# pidplate-mk-2_1.net
KiCad netlist of a schematic drawn in EAGLE
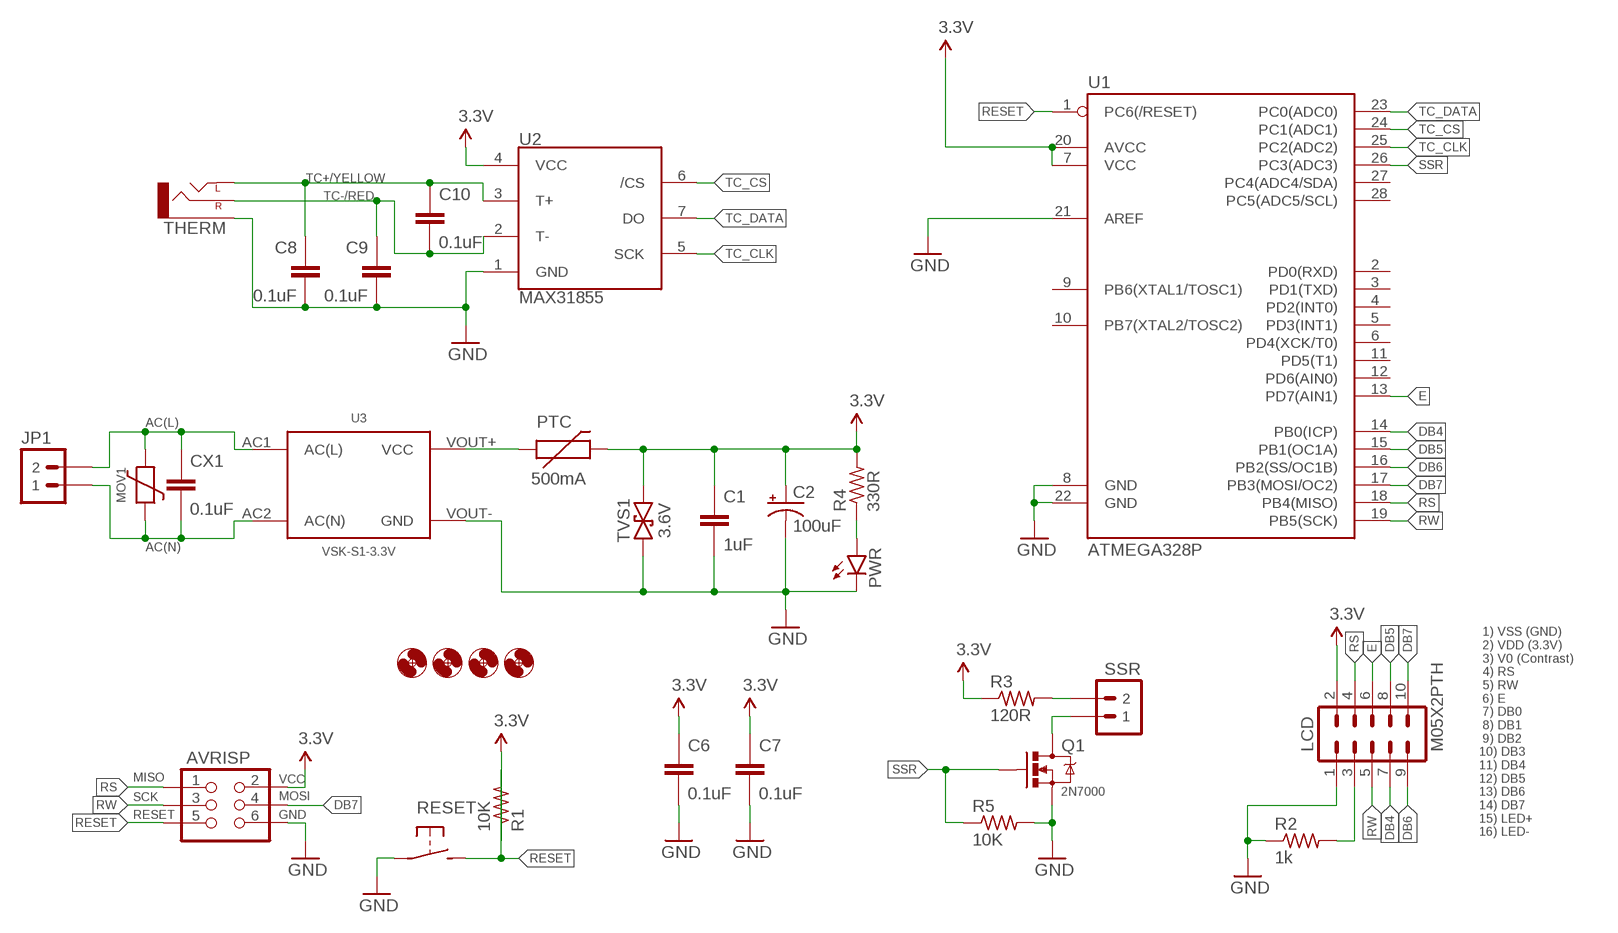
[diagram p0: schematic, sheet 1]

(export (version "E")
  (design (tool "Eeschema 10.0.6"))
  (components
    (comp (ref "AVRISP")
      (value "AVR_SPI_PRG_6PTH")
      (footprint "eagle-import:2X3")
      (libsource (lib "eagle-import") (part "AVR_SPI_PRG_6PTH"))
    )
    (comp (ref "C1")
      (value "1uF")
      (footprint "eagle-import:C025-024X044")
      (libsource (lib "eagle-import") (part "CAPACITOR-CERAMIC025-024X044"))
    )
    (comp (ref "C2")
      (value "100uF")
      (footprint "eagle-import:E2,5-7")
      (libsource (lib "eagle-import") (part "CAPACITOR-POLARIZEDE2.5-7"))
    )
    (comp (ref "C6")
      (value "0.1uF")
      (footprint "eagle-import:C025-024X044")
      (libsource (lib "eagle-import") (part "CAPACITOR-CERAMIC025-024X044"))
    )
    (comp (ref "C7")
      (value "0.1uF")
      (footprint "eagle-import:C025-024X044")
      (libsource (lib "eagle-import") (part "CAPACITOR-CERAMIC025-024X044"))
    )
    (comp (ref "C8")
      (value "0.1uF")
      (footprint "eagle-import:C025-024X044")
      (libsource (lib "eagle-import") (part "CAPACITOR-CERAMIC025-024X044"))
    )
    (comp (ref "C9")
      (value "0.1uF")
      (footprint "eagle-import:C025-024X044")
      (libsource (lib "eagle-import") (part "CAPACITOR-CERAMIC025-024X044"))
    )
    (comp (ref "C10")
      (value "0.1uF")
      (footprint "eagle-import:C025-024X044")
      (libsource (lib "eagle-import") (part "CAPACITOR-CERAMIC025-024X044"))
    )
    (comp (ref "CX1")
      (value "0.1uF")
      (footprint "eagle-import:XC10B5")
      (libsource (lib "eagle-import") (part "CXXC10B5"))
    )
    (comp (ref "H1")
      (value "HOLE#2")
      (footprint "eagle-import:HOLE-#2")
      (libsource (lib "eagle-import") (part "HOLE#2"))
    )
    (comp (ref "H2")
      (value "HOLE#2")
      (footprint "eagle-import:HOLE-#2")
      (libsource (lib "eagle-import") (part "HOLE#2"))
    )
    (comp (ref "H3")
      (value "HOLE#2")
      (footprint "eagle-import:HOLE-#2")
      (libsource (lib "eagle-import") (part "HOLE#2"))
    )
    (comp (ref "H4")
      (value "HOLE#2")
      (footprint "eagle-import:HOLE-#2")
      (libsource (lib "eagle-import") (part "HOLE#2"))
    )
    (comp (ref "JP1")
      (value "M023.5MM")
      (footprint "eagle-import:SCREWTERMINAL-3.5MM-2")
      (libsource (lib "eagle-import") (part "M023.5MM"))
    )
    (comp (ref "LCD")
      (value "M05X2PTH")
      (footprint "eagle-import:AVR_ICSP")
      (libsource (lib "eagle-import") (part "M05X2PTH"))
    )
    (comp (ref "MOV1")
      (value "VARISITORVAR-5.08MM-PTH")
      (footprint "eagle-import:VAR-5.08MM-PTH")
      (libsource (lib "eagle-import") (part "VARISITORVAR-5.08MM-PTH"))
    )
    (comp (ref "PTC")
      (value "500mA")
      (footprint "eagle-import:PTC")
      (libsource (lib "eagle-import") (part "PTCPTH"))
    )
    (comp (ref "PWR")
      (value "LED3MM")
      (footprint "eagle-import:LED3MM")
      (libsource (lib "eagle-import") (part "LED3MM"))
    )
    (comp (ref "Q1")
      (value "2N7000")
      (footprint "eagle-import:TO-92-AMMO")
      (libsource (lib "eagle-import") (part "MOSFET-NCHANNEL2N7000-AMMO"))
    )
    (comp (ref "R1")
      (value "10K")
      (footprint "eagle-import:RESISTOR-AXIAL-PTH-6.35MM")
      (libsource (lib "eagle-import") (part "RESISTORPTH-AXIAL-6.35MM"))
    )
    (comp (ref "R2")
      (value "1k")
      (footprint "eagle-import:RESISTOR-AXIAL-PTH-6.35MM")
      (libsource (lib "eagle-import") (part "RESISTORPTH-AXIAL-6.35MM"))
    )
    (comp (ref "R3")
      (value "120R")
      (footprint "eagle-import:RESISTOR-AXIAL-PTH-6.35MM")
      (libsource (lib "eagle-import") (part "RESISTORPTH-AXIAL-6.35MM"))
    )
    (comp (ref "R4")
      (value "330R")
      (footprint "eagle-import:RESISTOR-AXIAL-PTH-6.35MM")
      (libsource (lib "eagle-import") (part "RESISTORPTH-AXIAL-6.35MM"))
    )
    (comp (ref "R5")
      (value "10K")
      (footprint "eagle-import:RESISTOR-AXIAL-PTH-6.35MM")
      (libsource (lib "eagle-import") (part "RESISTORPTH-AXIAL-6.35MM"))
    )
    (comp (ref "RESET")
      (value "SPST-NO-TACT3MM-PTH-SMALL-PADS")
      (footprint "eagle-import:DTS-3-SMALL-PADS")
      (libsource (lib "eagle-import") (part "SPST-NO-TACT3MM-PTH-SMALL-PADS"))
    )
    (comp (ref "SSR")
      (value "M02JST-PTH-VERT")
      (footprint "eagle-import:JST-2-PH-VERT-PTH")
      (libsource (lib "eagle-import") (part "M02JST-PTH-VERT"))
    )
    (comp (ref "THERM")
      (value "AUDIO-JACK2.5MM")
      (footprint "eagle-import:STEREOJACK2.5MM_STEREOJACK2.5MM")
      (libsource (lib "eagle-import") (part "AUDIO-JACK2.5MM"))
    )
    (comp (ref "TVS1")
      (value "3.6V")
      (footprint "eagle-import:DO-41-TVS")
      (libsource (lib "eagle-import") (part "TVSDO-41-TVS-BIDIRECTIONAL"))
    )
    (comp (ref "U1")
      (value "ATMEGA328P")
      (footprint "eagle-import:DIL28-3")
      (libsource (lib "eagle-import") (part "ATMEGA328P_PDIP"))
    )
    (comp (ref "U2")
      (value "MAX31855")
      (footprint "eagle-import:SOIC127P600X175-8N")
      (libsource (lib "eagle-import") (part "MAX31855SOIC"))
    )
    (comp (ref "U3")
      (value "VSK-S1-3.3V")
      (footprint "eagle-import:VSK-S1")
      (libsource (lib "eagle-import") (part "VSK-S1"))
    )
  )
  (nets
    (net (code "1") (name "/AC(L)") (class "Default")
      (node (ref "CX1") (pin "1") (pinfunction "1_1") (pintype "passive"))
      (node (ref "JP1") (pin "2") (pinfunction "2_2") (pintype "passive"))
      (node (ref "MOV1") (pin "2") (pinfunction "P$2_2") (pintype "bidirectional"))
      (node (ref "U3") (pin "AC1") (pinfunction "AC(L)_AC1") (pintype "bidirectional"))
    )
    (net (code "2") (name "/AC(N)") (class "Default")
      (node (ref "CX1") (pin "2") (pinfunction "2_2") (pintype "passive"))
      (node (ref "JP1") (pin "1") (pinfunction "1_1") (pintype "passive"))
      (node (ref "MOV1") (pin "1") (pinfunction "P$1_1") (pintype "bidirectional"))
      (node (ref "U3") (pin "AC2") (pinfunction "AC(N)_AC2") (pintype "bidirectional"))
    )
    (net (code "3") (name "/TC+{slash}YELLOW") (class "Default")
      (node (ref "C10") (pin "1") (pinfunction "1_1") (pintype "passive"))
      (node (ref "C8") (pin "1") (pinfunction "1_1") (pintype "passive"))
      (node (ref "THERM") (pin "RING1") (pinfunction "LEFT_RING1") (pintype "bidirectional"))
      (node (ref "THERM") (pin "RING2") (pinfunction "LEFT_RING2") (pintype "bidirectional"))
      (node (ref "U2") (pin "3") (pinfunction "T+_3") (pintype "input"))
    )
    (net (code "4") (name "/TC-{slash}RED") (class "Default")
      (node (ref "C10") (pin "2") (pinfunction "2_2") (pintype "passive"))
      (node (ref "C9") (pin "1") (pinfunction "1_1") (pintype "passive"))
      (node (ref "THERM") (pin "TIP") (pinfunction "RIGHT_TIP") (pintype "bidirectional"))
      (node (ref "U2") (pin "2") (pinfunction "T-_2") (pintype "input"))
    )
    (net (code "5") (name "3.3V") (class "Default")
      (node (ref "AVRISP") (pin "2") (pinfunction "VCC_2") (pintype "passive"))
      (node (ref "C1") (pin "1") (pinfunction "1_1") (pintype "passive"))
      (node (ref "C2") (pin "+") (pinfunction "+_+") (pintype "passive"))
      (node (ref "C6") (pin "1") (pinfunction "1_1") (pintype "passive"))
      (node (ref "C7") (pin "1") (pinfunction "1_1") (pintype "passive"))
      (node (ref "LCD") (pin "2") (pinfunction "2_2") (pintype "passive"))
      (node (ref "PTC") (pin "P$2") (pinfunction "2_P$2") (pintype "bidirectional"))
      (node (ref "R1") (pin "P$1") (pinfunction "1_P$1") (pintype "passive"))
      (node (ref "R3") (pin "P$1") (pinfunction "1_P$1") (pintype "passive"))
      (node (ref "R4") (pin "P$2") (pinfunction "2_P$2") (pintype "passive"))
      (node (ref "TVS1") (pin "P$2") (pinfunction "2_P$2") (pintype "passive"))
      (node (ref "U1") (pin "20") (pinfunction "AVCC_20") (pintype "bidirectional"))
      (node (ref "U1") (pin "7") (pinfunction "VCC_7") (pintype "bidirectional"))
      (node (ref "U2") (pin "4") (pinfunction "VCC_4") (pintype "power_in"))
    )
    (net (code "6") (name "DB4") (class "Default")
      (node (ref "LCD") (pin "7") (pinfunction "7_7") (pintype "passive"))
      (node (ref "U1") (pin "14") (pinfunction "PB0(ICP)_14") (pintype "bidirectional"))
    )
    (net (code "7") (name "DB5") (class "Default")
      (node (ref "LCD") (pin "8") (pinfunction "8_8") (pintype "passive"))
      (node (ref "U1") (pin "15") (pinfunction "PB1(OC1A)_15") (pintype "bidirectional"))
    )
    (net (code "8") (name "DB6") (class "Default")
      (node (ref "LCD") (pin "9") (pinfunction "9_9") (pintype "passive"))
      (node (ref "U1") (pin "16") (pinfunction "PB2(SS/OC1B)_16") (pintype "bidirectional"))
    )
    (net (code "9") (name "DB7") (class "Default")
      (node (ref "AVRISP") (pin "4") (pinfunction "MOSI_4") (pintype "passive"))
      (node (ref "LCD") (pin "10") (pinfunction "10_10") (pintype "passive"))
      (node (ref "U1") (pin "17") (pinfunction "PB3(MOSI/OC2)_17") (pintype "bidirectional"))
    )
    (net (code "10") (name "E") (class "Default")
      (node (ref "LCD") (pin "6") (pinfunction "6_6") (pintype "passive"))
      (node (ref "U1") (pin "13") (pinfunction "PD7(AIN1)_13") (pintype "bidirectional"))
    )
    (net (code "11") (name "GND") (class "Default")
      (node (ref "AVRISP") (pin "6") (pinfunction "GND_6") (pintype "passive"))
      (node (ref "C1") (pin "2") (pinfunction "2_2") (pintype "passive"))
      (node (ref "C2") (pin "-") (pinfunction "-_-") (pintype "passive"))
      (node (ref "C6") (pin "2") (pinfunction "2_2") (pintype "passive"))
      (node (ref "C7") (pin "2") (pinfunction "2_2") (pintype "passive"))
      (node (ref "C8") (pin "2") (pinfunction "2_2") (pintype "passive"))
      (node (ref "C9") (pin "2") (pinfunction "2_2") (pintype "passive"))
      (node (ref "LCD") (pin "1") (pinfunction "1_1") (pintype "passive"))
      (node (ref "PWR") (pin "K") (pinfunction "C_K") (pintype "passive"))
      (node (ref "Q1") (pin "1") (pinfunction "S_1") (pintype "passive"))
      (node (ref "R2") (pin "P$1") (pinfunction "1_P$1") (pintype "passive"))
      (node (ref "R5") (pin "P$2") (pinfunction "2_P$2") (pintype "passive"))
      (node (ref "RESET") (pin "1") (pinfunction "1_1") (pintype "passive"))
      (node (ref "THERM") (pin "SHIELD") (pinfunction "SLEEVE_SHIELD") (pintype "bidirectional"))
      (node (ref "TVS1") (pin "P$1") (pinfunction "1_P$1") (pintype "passive"))
      (node (ref "U1") (pin "21") (pinfunction "AREF_21") (pintype "bidirectional"))
      (node (ref "U1") (pin "22") (pinfunction "GND_22") (pintype "bidirectional"))
      (node (ref "U1") (pin "8") (pinfunction "GND_8") (pintype "bidirectional"))
      (node (ref "U2") (pin "1") (pinfunction "GND_1") (pintype "power_in"))
      (node (ref "U3") (pin "VOUT-") (pinfunction "GND_VOUT-") (pintype "bidirectional"))
    )
    (net (code "12") (name "Net-(PTC-1)") (class "Default")
      (node (ref "PTC") (pin "P$1") (pinfunction "1_P$1") (pintype "bidirectional"))
      (node (ref "U3") (pin "VOUT+") (pinfunction "VCC_VOUT+") (pintype "bidirectional"))
    )
    (net (code "13") (name "Net-(Q1-D)") (class "Default")
      (node (ref "Q1") (pin "3") (pinfunction "D_3") (pintype "passive"))
      (node (ref "SSR") (pin "1") (pinfunction "1_1") (pintype "passive"))
    )
    (net (code "14") (name "Net-(R2-2)") (class "Default")
      (node (ref "LCD") (pin "3") (pinfunction "3_3") (pintype "passive"))
      (node (ref "R2") (pin "P$2") (pinfunction "2_P$2") (pintype "passive"))
    )
    (net (code "15") (name "Net-(R3-2)") (class "Default")
      (node (ref "R3") (pin "P$2") (pinfunction "2_P$2") (pintype "passive"))
      (node (ref "SSR") (pin "2") (pinfunction "2_2") (pintype "passive"))
    )
    (net (code "16") (name "Net-(R4-1)") (class "Default")
      (node (ref "PWR") (pin "A") (pinfunction "A_A") (pintype "passive"))
      (node (ref "R4") (pin "P$1") (pinfunction "1_P$1") (pintype "passive"))
    )
    (net (code "17") (name "RESET") (class "Default")
      (node (ref "AVRISP") (pin "5") (pinfunction "RESET_5") (pintype "passive"))
      (node (ref "R1") (pin "P$2") (pinfunction "2_P$2") (pintype "passive"))
      (node (ref "RESET") (pin "2") (pinfunction "2_2") (pintype "passive"))
      (node (ref "U1") (pin "1") (pinfunction "PC6(/RESET)_1") (pintype "bidirectional"))
    )
    (net (code "18") (name "RS") (class "Default")
      (node (ref "AVRISP") (pin "1") (pinfunction "MISO_1") (pintype "passive"))
      (node (ref "LCD") (pin "4") (pinfunction "4_4") (pintype "passive"))
      (node (ref "U1") (pin "18") (pinfunction "PB4(MISO)_18") (pintype "bidirectional"))
    )
    (net (code "19") (name "RW") (class "Default")
      (node (ref "AVRISP") (pin "3") (pinfunction "SCK_3") (pintype "passive"))
      (node (ref "LCD") (pin "5") (pinfunction "5_5") (pintype "passive"))
      (node (ref "U1") (pin "19") (pinfunction "PB5(SCK)_19") (pintype "bidirectional"))
    )
    (net (code "20") (name "SSR") (class "Default")
      (node (ref "Q1") (pin "2") (pinfunction "G_2") (pintype "passive"))
      (node (ref "R5") (pin "P$1") (pinfunction "1_P$1") (pintype "passive"))
      (node (ref "U1") (pin "26") (pinfunction "PC3(ADC3)_26") (pintype "bidirectional"))
    )
    (net (code "21") (name "TC_CLK") (class "Default")
      (node (ref "U1") (pin "25") (pinfunction "PC2(ADC2)_25") (pintype "bidirectional"))
      (node (ref "U2") (pin "5") (pinfunction "SCK_5") (pintype "input"))
    )
    (net (code "22") (name "TC_CS") (class "Default")
      (node (ref "U1") (pin "24") (pinfunction "PC1(ADC1)_24") (pintype "bidirectional"))
      (node (ref "U2") (pin "6") (pinfunction "/CS_6") (pintype "input"))
    )
    (net (code "23") (name "TC_DATA") (class "Default")
      (node (ref "U1") (pin "23") (pinfunction "PC0(ADC0)_23") (pintype "bidirectional"))
      (node (ref "U2") (pin "7") (pinfunction "DO_7") (pintype "output"))
    )
    (net (code "24") (name "unconnected-(U1-PB6(XTAL1{slash}TOSC1)-Pad9)") (class "Default")
      (node (ref "U1") (pin "9") (pinfunction "PB6(XTAL1/TOSC1)_9") (pintype "bidirectional"))
    )
    (net (code "25") (name "unconnected-(U1-PB7(XTAL2{slash}TOSC2)-Pad10)") (class "Default")
      (node (ref "U1") (pin "10") (pinfunction "PB7(XTAL2/TOSC2)_10") (pintype "bidirectional"))
    )
    (net (code "26") (name "unconnected-(U1-PC4(ADC4{slash}SDA)-Pad27)") (class "Default")
      (node (ref "U1") (pin "27") (pinfunction "PC4(ADC4/SDA)_27") (pintype "bidirectional"))
    )
    (net (code "27") (name "unconnected-(U1-PC5(ADC5{slash}SCL)-Pad28)") (class "Default")
      (node (ref "U1") (pin "28") (pinfunction "PC5(ADC5/SCL)_28") (pintype "bidirectional"))
    )
    (net (code "28") (name "unconnected-(U1-PD0(RXD)-Pad2)") (class "Default")
      (node (ref "U1") (pin "2") (pinfunction "PD0(RXD)_2") (pintype "bidirectional"))
    )
    (net (code "29") (name "unconnected-(U1-PD1(TXD)-Pad3)") (class "Default")
      (node (ref "U1") (pin "3") (pinfunction "PD1(TXD)_3") (pintype "bidirectional"))
    )
    (net (code "30") (name "unconnected-(U1-PD2(INT0)-Pad4)") (class "Default")
      (node (ref "U1") (pin "4") (pinfunction "PD2(INT0)_4") (pintype "bidirectional"))
    )
    (net (code "31") (name "unconnected-(U1-PD3(INT1)-Pad5)") (class "Default")
      (node (ref "U1") (pin "5") (pinfunction "PD3(INT1)_5") (pintype "bidirectional"))
    )
    (net (code "32") (name "unconnected-(U1-PD4(XCK{slash}T0)-Pad6)") (class "Default")
      (node (ref "U1") (pin "6") (pinfunction "PD4(XCK/T0)_6") (pintype "bidirectional"))
    )
    (net (code "33") (name "unconnected-(U1-PD5(T1)-Pad11)") (class "Default")
      (node (ref "U1") (pin "11") (pinfunction "PD5(T1)_11") (pintype "bidirectional"))
    )
    (net (code "34") (name "unconnected-(U1-PD6(AIN0)-Pad12)") (class "Default")
      (node (ref "U1") (pin "12") (pinfunction "PD6(AIN0)_12") (pintype "bidirectional"))
    )
  )
)
